# MotorControllerChipTest.net
KiCad netlist of a schematic drawn in EAGLE
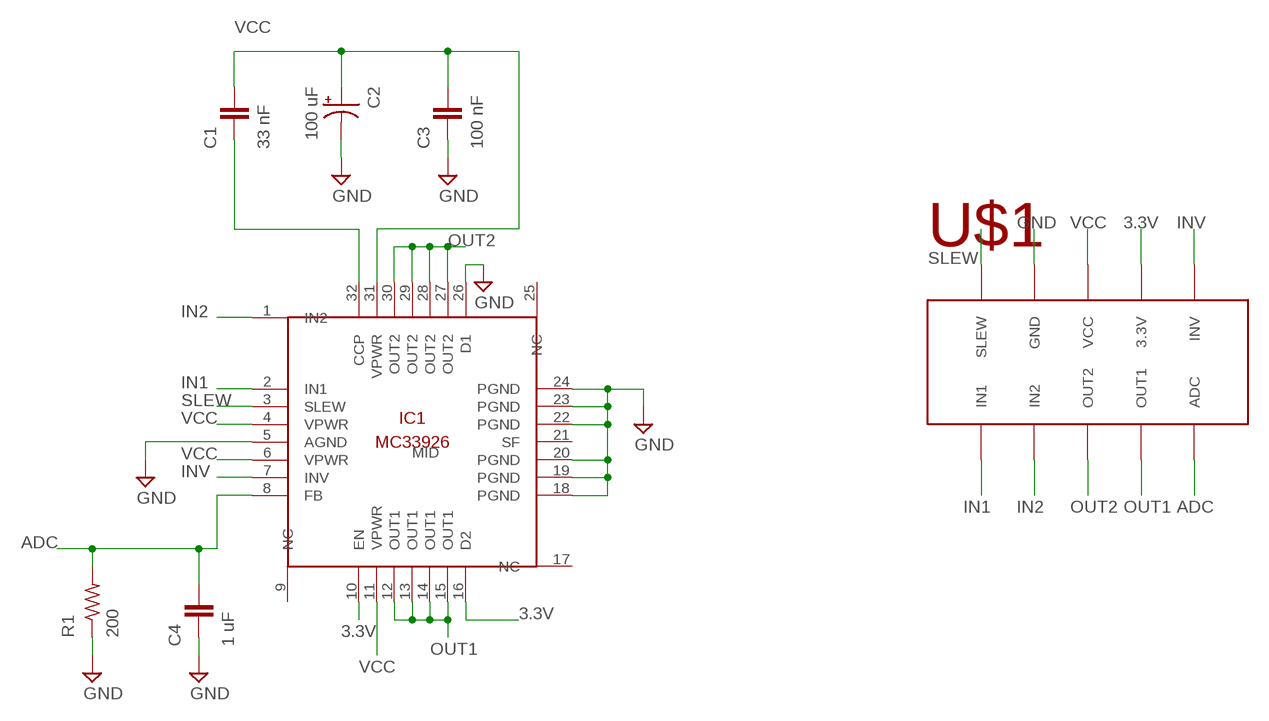
[diagram p0: schematic, sheet 1]

(export (version "E")
  (design (tool "Eeschema 10.0.6"))
  (components
    (comp (ref "C1")
      (value "33 nF")
      (footprint "eagle-import:0603-CAP")
      (libsource (lib "eagle-import") (part "CAP0603-CAP"))
    )
    (comp (ref "C2")
      (value "100 uF")
      (footprint "eagle-import:.248_CAP_THRU")
      (libsource (lib "eagle-import") (part "CAP_POLRADIAL"))
    )
    (comp (ref "C3")
      (value "100 nF")
      (footprint "eagle-import:0603-CAP")
      (libsource (lib "eagle-import") (part "CAP0603-CAP"))
    )
    (comp (ref "C4")
      (value "1 uF")
      (footprint "eagle-import:0603-CAP")
      (libsource (lib "eagle-import") (part "CAP0603-CAP"))
    )
    (comp (ref "IC1")
      (value "MC33926")
      (footprint "eagle-import:PQFN-32")
      (libsource (lib "eagle-import") (part "MC33926"))
    )
    (comp (ref "R1")
      (value "200")
      (footprint "eagle-import:R0603")
      (fields (field (name "MANUFACTURER") "Rohm Semiconductor"))
      (libsource (lib "eagle-import") (part "R-US_R0603"))
    )
    (comp (ref "U$1")
      (value "2X5PIN")
      (footprint "eagle-import:2X5PIN")
      (libsource (lib "eagle-import") (part "2X5PIN"))
    )
  )
  (nets
    (net (code "1") (name "/3.3V") (class "Default")
      (node (ref "IC1") (pin "10") (pinfunction "EN_10") (pintype "bidirectional"))
      (node (ref "IC1") (pin "16") (pinfunction "D2_16") (pintype "bidirectional"))
      (node (ref "U$1") (pin "3.3V") (pinfunction "3.3V_3.3V") (pintype "bidirectional"))
    )
    (net (code "2") (name "/ADC") (class "Default")
      (node (ref "C4") (pin "2") (pinfunction "2_2") (pintype "passive"))
      (node (ref "IC1") (pin "8") (pinfunction "FB_8") (pintype "bidirectional"))
      (node (ref "R1") (pin "2") (pinfunction "2_2") (pintype "passive"))
      (node (ref "U$1") (pin "ADC") (pinfunction "ADC_ADC") (pintype "bidirectional"))
    )
    (net (code "3") (name "/IN1") (class "Default")
      (node (ref "IC1") (pin "2") (pinfunction "IN1_2") (pintype "bidirectional"))
      (node (ref "U$1") (pin "IN1") (pinfunction "IN1_IN1") (pintype "bidirectional"))
    )
    (net (code "4") (name "/IN2") (class "Default")
      (node (ref "IC1") (pin "1") (pinfunction "IN2_1") (pintype "bidirectional"))
      (node (ref "U$1") (pin "IN2") (pinfunction "IN2_IN2") (pintype "bidirectional"))
    )
    (net (code "5") (name "/INV") (class "Default")
      (node (ref "IC1") (pin "7") (pinfunction "INV_7") (pintype "bidirectional"))
      (node (ref "U$1") (pin "INV") (pinfunction "INV_INV") (pintype "bidirectional"))
    )
    (net (code "6") (name "/OUT1") (class "Default")
      (node (ref "IC1") (pin "12") (pinfunction "OUT1_12") (pintype "bidirectional"))
      (node (ref "IC1") (pin "13") (pinfunction "OUT1_13") (pintype "bidirectional"))
      (node (ref "IC1") (pin "14") (pinfunction "OUT1_14") (pintype "bidirectional"))
      (node (ref "IC1") (pin "15") (pinfunction "OUT1_15") (pintype "bidirectional"))
      (node (ref "U$1") (pin "OUT1") (pinfunction "OUT1_OUT1") (pintype "bidirectional"))
    )
    (net (code "7") (name "/OUT2") (class "Default")
      (node (ref "IC1") (pin "27") (pinfunction "OUT2_27") (pintype "bidirectional"))
      (node (ref "IC1") (pin "28") (pinfunction "OUT2_28") (pintype "bidirectional"))
      (node (ref "IC1") (pin "29") (pinfunction "OUT2_29") (pintype "bidirectional"))
      (node (ref "IC1") (pin "30") (pinfunction "OUT2_30") (pintype "bidirectional"))
      (node (ref "U$1") (pin "OUT2") (pinfunction "OUT2_OUT2") (pintype "bidirectional"))
    )
    (net (code "8") (name "/SLEW") (class "Default")
      (node (ref "IC1") (pin "3") (pinfunction "SLEW_3") (pintype "bidirectional"))
      (node (ref "U$1") (pin "SLEW") (pinfunction "SLEW_SLEW") (pintype "bidirectional"))
    )
    (net (code "9") (name "/VCC") (class "Default")
      (node (ref "C1") (pin "2") (pinfunction "2_2") (pintype "passive"))
      (node (ref "C2") (pin "PLUS") (pinfunction "+_PLUS") (pintype "passive"))
      (node (ref "C3") (pin "2") (pinfunction "2_2") (pintype "passive"))
      (node (ref "IC1") (pin "11") (pinfunction "VPWR_11") (pintype "bidirectional"))
      (node (ref "IC1") (pin "31") (pinfunction "VPWR_31") (pintype "bidirectional"))
      (node (ref "IC1") (pin "4") (pinfunction "VPWR_4") (pintype "bidirectional"))
      (node (ref "IC1") (pin "6") (pinfunction "VPWR_6") (pintype "bidirectional"))
      (node (ref "U$1") (pin "VCC") (pinfunction "VCC_VCC") (pintype "bidirectional"))
    )
    (net (code "10") (name "GND") (class "Default")
      (node (ref "C2") (pin "MINUS") (pinfunction "-_MINUS") (pintype "passive"))
      (node (ref "C3") (pin "1") (pinfunction "1_1") (pintype "passive"))
      (node (ref "C4") (pin "1") (pinfunction "1_1") (pintype "passive"))
      (node (ref "IC1") (pin "18") (pinfunction "PGND_18") (pintype "bidirectional"))
      (node (ref "IC1") (pin "19") (pinfunction "PGND_19") (pintype "bidirectional"))
      (node (ref "IC1") (pin "20") (pinfunction "PGND_20") (pintype "bidirectional"))
      (node (ref "IC1") (pin "22") (pinfunction "PGND_22") (pintype "bidirectional"))
      (node (ref "IC1") (pin "23") (pinfunction "PGND_23") (pintype "bidirectional"))
      (node (ref "IC1") (pin "24") (pinfunction "PGND_24") (pintype "bidirectional"))
      (node (ref "IC1") (pin "26") (pinfunction "D1_26") (pintype "bidirectional"))
      (node (ref "IC1") (pin "5") (pinfunction "AGND_5") (pintype "bidirectional"))
      (node (ref "R1") (pin "1") (pinfunction "1_1") (pintype "passive"))
      (node (ref "U$1") (pin "GND") (pinfunction "GND_GND") (pintype "bidirectional"))
    )
    (net (code "11") (name "Net-(IC1-CCP)") (class "Default")
      (node (ref "C1") (pin "1") (pinfunction "1_1") (pintype "passive"))
      (node (ref "IC1") (pin "32") (pinfunction "CCP_32") (pintype "bidirectional"))
    )
    (net (code "12") (name "unconnected-(IC1-AGND-PadMID)") (class "Default")
      (node (ref "IC1") (pin "MID") (pinfunction "AGND_MID") (pintype "bidirectional"))
    )
    (net (code "13") (name "unconnected-(IC1-NC-Pad9)") (class "Default")
      (node (ref "IC1") (pin "9") (pinfunction "NC_9") (pintype "bidirectional"))
    )
    (net (code "14") (name "unconnected-(IC1-NC-Pad17)") (class "Default")
      (node (ref "IC1") (pin "17") (pinfunction "NC_17") (pintype "bidirectional"))
    )
    (net (code "15") (name "unconnected-(IC1-NC-Pad25)") (class "Default")
      (node (ref "IC1") (pin "25") (pinfunction "NC_25") (pintype "bidirectional"))
    )
    (net (code "16") (name "unconnected-(IC1-SF-Pad21)") (class "Default")
      (node (ref "IC1") (pin "21") (pinfunction "SF_21") (pintype "bidirectional"))
    )
  )
)
